# step_up_actuator.net
KiCad netlist of a schematic drawn in EAGLE
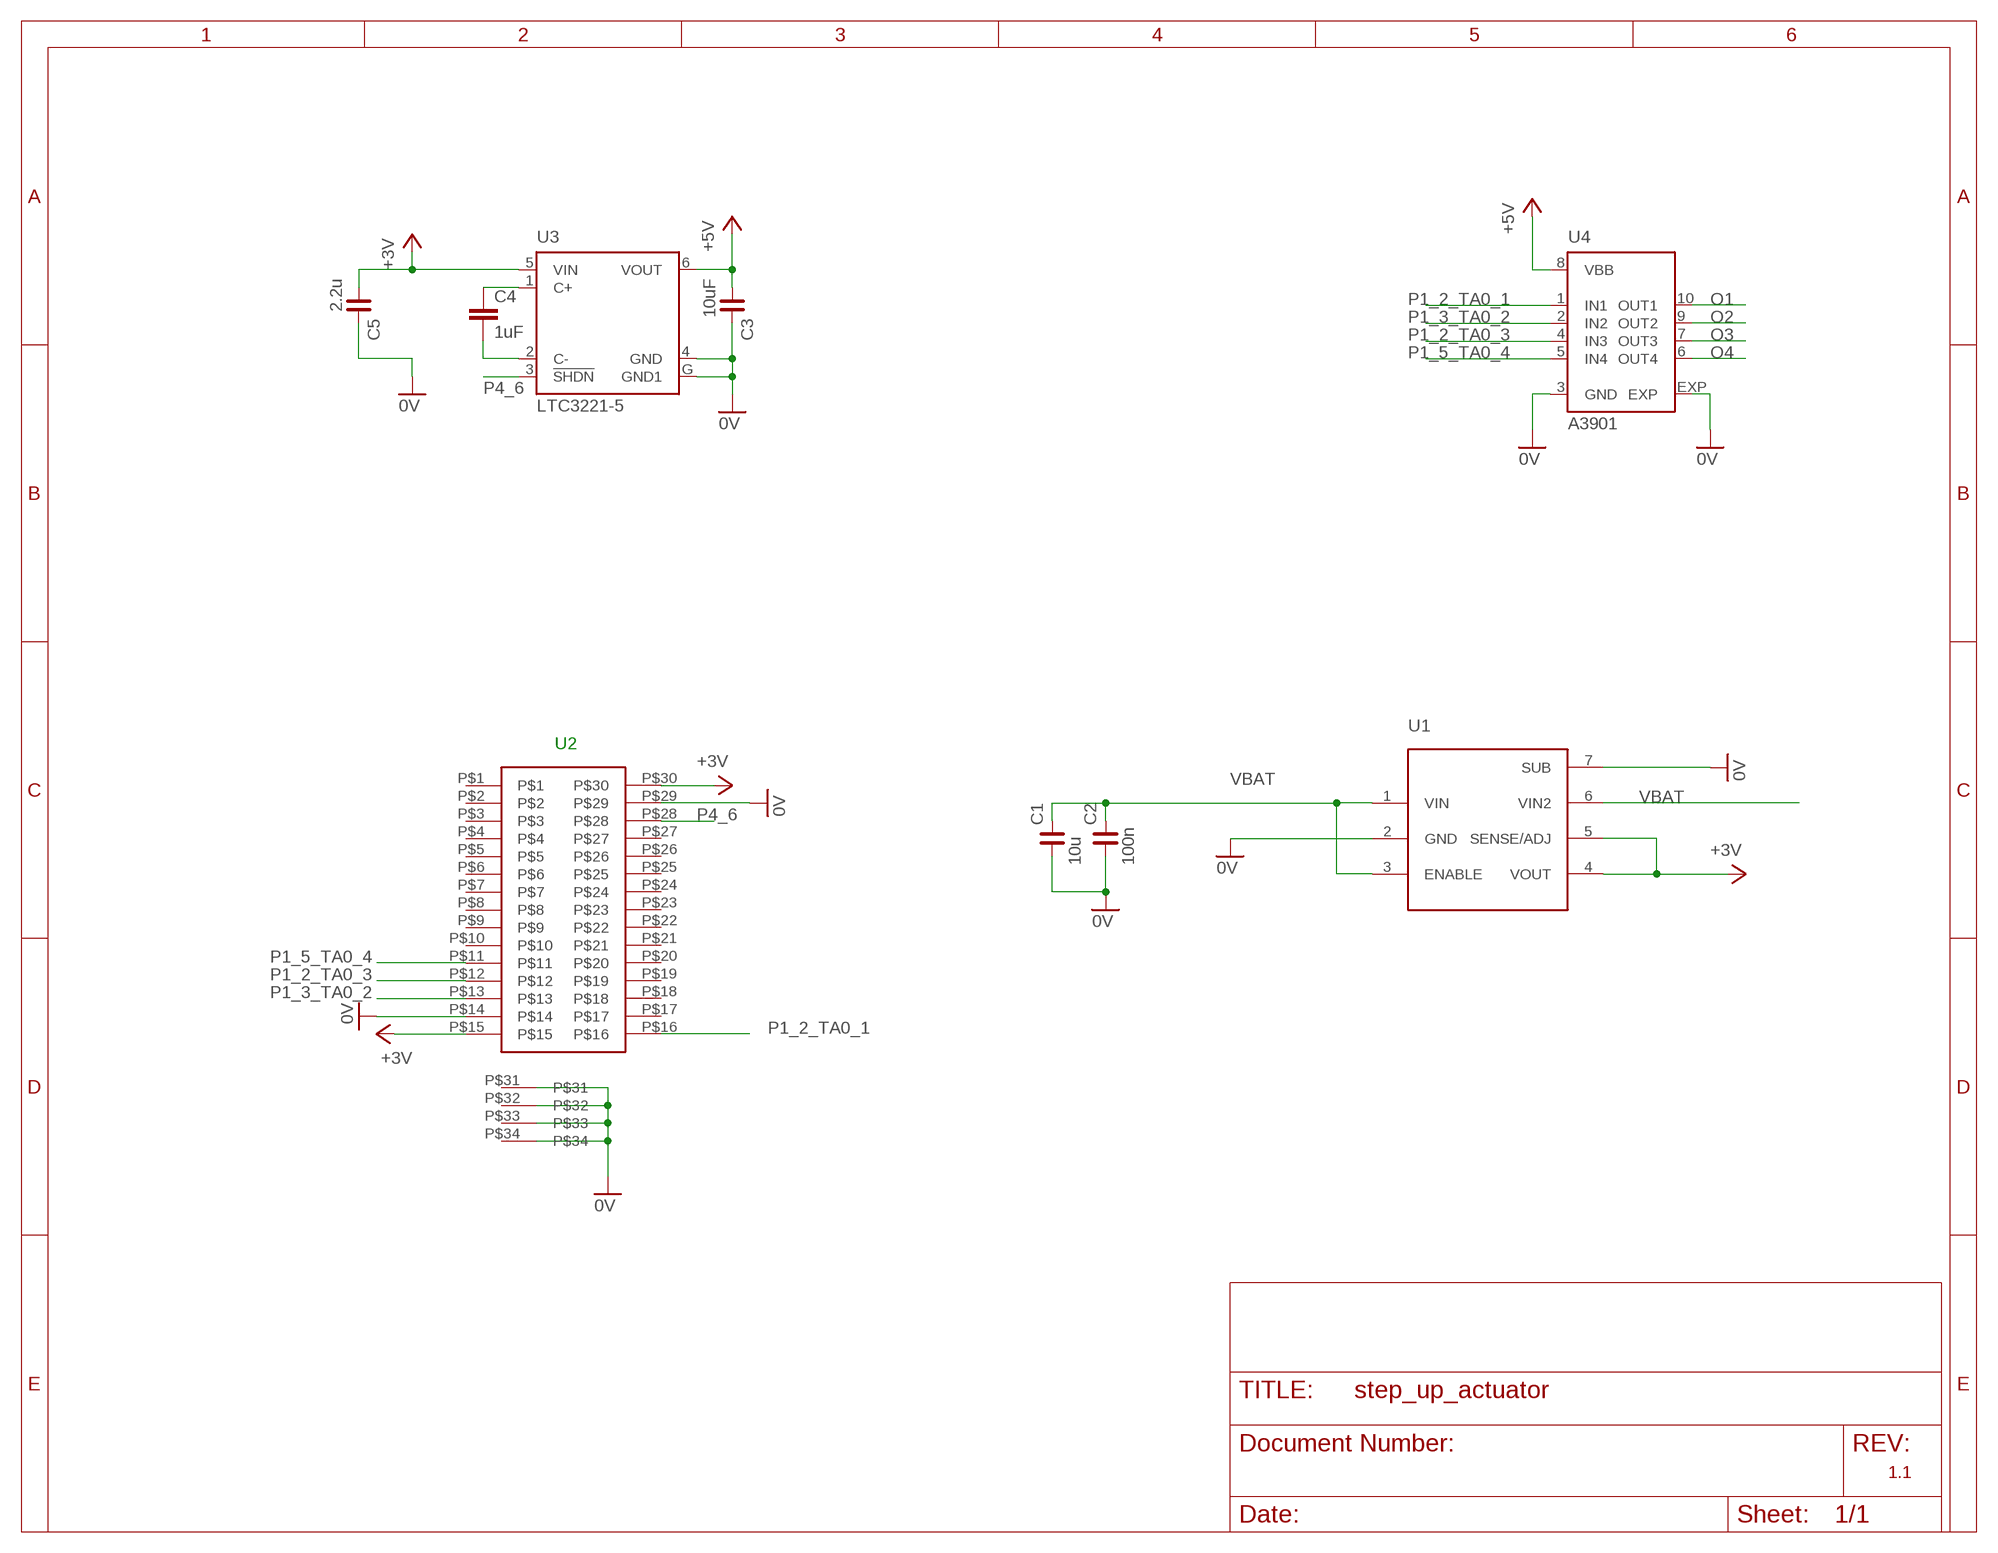
[diagram p0: schematic, sheet 1]

(export (version "E")
  (design (tool "Eeschema 10.0.6"))
  (components
    (comp (ref "C1")
      (value "10u")
      (footprint "eagle-import:C0402")
      (libsource (lib "eagle-import") (part "C_0402"))
    )
    (comp (ref "C2")
      (value "100n")
      (footprint "eagle-import:C0402")
      (libsource (lib "eagle-import") (part "C_0402"))
    )
    (comp (ref "C3")
      (value "10uF")
      (footprint "eagle-import:C1206")
      (libsource (lib "eagle-import") (part "C_1206"))
    )
    (comp (ref "C4")
      (value "1uF")
      (footprint "eagle-import:C0402")
      (libsource (lib "eagle-import") (part "C-EUC0402"))
    )
    (comp (ref "C5")
      (value "2.2u")
      (footprint "eagle-import:C0402")
      (libsource (lib "eagle-import") (part "C_0402"))
    )
    (comp (ref "U$1")
      (value "NCP606")
      (footprint "eagle-import:NCP606")
      (libsource (lib "eagle-import") (part "NCP606"))
    )
    (comp (ref "U$3")
      (value "51338-0374_RECEPTACLE")
      (footprint "eagle-import:51338-0374_RECEPTACLE")
      (libsource (lib "eagle-import") (part "51338-0374_RECEPTACLE"))
    )
    (comp (ref "U3")
      (value "LTC3221-5")
      (footprint "eagle-import:DFN6-2X2")
      (libsource (lib "eagle-import") (part "LTC3221-5"))
    )
    (comp (ref "U4")
      (value "A3901")
      (footprint "eagle-import:DFN10-3X3")
      (fields (field (name "MPN") "A3901SEJTR-T"))
      (libsource (lib "eagle-import") (part "A3901"))
    )
  )
  (nets
    (net (code "1") (name "+3V") (class "Default")
      (node (ref "C5") (pin "1") (pinfunction "1_1") (pintype "passive"))
      (node (ref "U$1") (pin "4") (pinfunction "VOUT_4") (pintype "bidirectional"))
      (node (ref "U$1") (pin "5") (pinfunction "SENSE/ADJ_5") (pintype "bidirectional"))
      (node (ref "U$3") (pin "P$15") (pinfunction "P$15_P$15") (pintype "bidirectional"))
      (node (ref "U$3") (pin "P$30") (pinfunction "P$30_P$30") (pintype "bidirectional"))
      (node (ref "U3") (pin "5") (pinfunction "VIN_5") (pintype "input"))
    )
    (net (code "2") (name "+5V") (class "Default")
      (node (ref "C3") (pin "1") (pinfunction "1_1") (pintype "passive"))
      (node (ref "U3") (pin "6") (pinfunction "VOUT_6") (pintype "output"))
      (node (ref "U4") (pin "8") (pinfunction "VBB_8") (pintype "power_in"))
    )
    (net (code "3") (name "/O1") (class "Default")
      (node (ref "U4") (pin "10") (pinfunction "OUT1_10") (pintype "output"))
    )
    (net (code "4") (name "/O2") (class "Default")
      (node (ref "U4") (pin "9") (pinfunction "OUT2_9") (pintype "output"))
    )
    (net (code "5") (name "/O3") (class "Default")
      (node (ref "U4") (pin "7") (pinfunction "OUT3_7") (pintype "output"))
    )
    (net (code "6") (name "/O4") (class "Default")
      (node (ref "U4") (pin "6") (pinfunction "OUT4_6") (pintype "output"))
    )
    (net (code "7") (name "/P1_2_TA0_1") (class "Default")
      (node (ref "U$3") (pin "P$16") (pinfunction "P$16_P$16") (pintype "bidirectional"))
      (node (ref "U4") (pin "1") (pinfunction "IN1_1") (pintype "input"))
    )
    (net (code "8") (name "/P1_2_TA0_3") (class "Default")
      (node (ref "U$3") (pin "P$12") (pinfunction "P$12_P$12") (pintype "bidirectional"))
      (node (ref "U4") (pin "4") (pinfunction "IN3_4") (pintype "input"))
    )
    (net (code "9") (name "/P1_3_TA0_2") (class "Default")
      (node (ref "U$3") (pin "P$13") (pinfunction "P$13_P$13") (pintype "bidirectional"))
      (node (ref "U4") (pin "2") (pinfunction "IN2_2") (pintype "input"))
    )
    (net (code "10") (name "/P1_5_TA0_4") (class "Default")
      (node (ref "U$3") (pin "P$11") (pinfunction "P$11_P$11") (pintype "bidirectional"))
      (node (ref "U4") (pin "5") (pinfunction "IN4_5") (pintype "input"))
    )
    (net (code "11") (name "/P4_6") (class "Default")
      (node (ref "U$3") (pin "P$28") (pinfunction "P$28_P$28") (pintype "bidirectional"))
      (node (ref "U3") (pin "3") (pinfunction "~{SHDN}_3") (pintype "input"))
    )
    (net (code "12") (name "/VBAT") (class "Default")
      (node (ref "C1") (pin "2") (pinfunction "2_2") (pintype "passive"))
      (node (ref "C2") (pin "2") (pinfunction "2_2") (pintype "passive"))
      (node (ref "U$1") (pin "1") (pinfunction "VIN_1") (pintype "bidirectional"))
      (node (ref "U$1") (pin "3") (pinfunction "ENABLE_3") (pintype "bidirectional"))
      (node (ref "U$1") (pin "6") (pinfunction "VIN2_6") (pintype "bidirectional"))
    )
    (net (code "13") (name "0V") (class "Default")
      (node (ref "C1") (pin "1") (pinfunction "1_1") (pintype "passive"))
      (node (ref "C2") (pin "1") (pinfunction "1_1") (pintype "passive"))
      (node (ref "C3") (pin "2") (pinfunction "2_2") (pintype "passive"))
      (node (ref "C5") (pin "2") (pinfunction "2_2") (pintype "passive"))
      (node (ref "U$1") (pin "2") (pinfunction "GND_2") (pintype "bidirectional"))
      (node (ref "U$1") (pin "7") (pinfunction "SUB_7") (pintype "bidirectional"))
      (node (ref "U$3") (pin "P$14") (pinfunction "P$14_P$14") (pintype "bidirectional"))
      (node (ref "U$3") (pin "P$29") (pinfunction "P$29_P$29") (pintype "bidirectional"))
      (node (ref "U3") (pin "4") (pinfunction "GND_4") (pintype "power_in"))
      (node (ref "U3") (pin "G") (pinfunction "GND1_G") (pintype "power_in"))
      (node (ref "U4") (pin "3") (pinfunction "GND_3") (pintype "power_in"))
      (node (ref "U4") (pin "EXP") (pinfunction "EXP_EXP") (pintype "passive"))
    )
    (net (code "14") (name "Net-(U3-C+)") (class "Default")
      (node (ref "C4") (pin "1") (pinfunction "1_1") (pintype "passive"))
      (node (ref "U3") (pin "1") (pinfunction "C+_1") (pintype "input"))
    )
    (net (code "15") (name "Net-(U3-C-)") (class "Default")
      (node (ref "C4") (pin "2") (pinfunction "2_2") (pintype "passive"))
      (node (ref "U3") (pin "2") (pinfunction "C-_2") (pintype "input"))
    )
    (net (code "16") (name "unconnected-(U$3-PadP$1)") (class "Default")
      (node (ref "U$3") (pin "P$1") (pinfunction "P$1_P$1") (pintype "bidirectional"))
    )
    (net (code "17") (name "unconnected-(U$3-PadP$2)") (class "Default")
      (node (ref "U$3") (pin "P$2") (pinfunction "P$2_P$2") (pintype "bidirectional"))
    )
    (net (code "18") (name "unconnected-(U$3-PadP$3)") (class "Default")
      (node (ref "U$3") (pin "P$3") (pinfunction "P$3_P$3") (pintype "bidirectional"))
    )
    (net (code "19") (name "unconnected-(U$3-PadP$4)") (class "Default")
      (node (ref "U$3") (pin "P$4") (pinfunction "P$4_P$4") (pintype "bidirectional"))
    )
    (net (code "20") (name "unconnected-(U$3-PadP$5)") (class "Default")
      (node (ref "U$3") (pin "P$5") (pinfunction "P$5_P$5") (pintype "bidirectional"))
    )
    (net (code "21") (name "unconnected-(U$3-PadP$6)") (class "Default")
      (node (ref "U$3") (pin "P$6") (pinfunction "P$6_P$6") (pintype "bidirectional"))
    )
    (net (code "22") (name "unconnected-(U$3-PadP$7)") (class "Default")
      (node (ref "U$3") (pin "P$7") (pinfunction "P$7_P$7") (pintype "bidirectional"))
    )
    (net (code "23") (name "unconnected-(U$3-PadP$8)") (class "Default")
      (node (ref "U$3") (pin "P$8") (pinfunction "P$8_P$8") (pintype "bidirectional"))
    )
    (net (code "24") (name "unconnected-(U$3-PadP$9)") (class "Default")
      (node (ref "U$3") (pin "P$9") (pinfunction "P$9_P$9") (pintype "bidirectional"))
    )
    (net (code "25") (name "unconnected-(U$3-PadP$10)") (class "Default")
      (node (ref "U$3") (pin "P$10") (pinfunction "P$10_P$10") (pintype "bidirectional"))
    )
    (net (code "26") (name "unconnected-(U$3-PadP$17)") (class "Default")
      (node (ref "U$3") (pin "P$17") (pinfunction "P$17_P$17") (pintype "bidirectional"))
    )
    (net (code "27") (name "unconnected-(U$3-PadP$18)") (class "Default")
      (node (ref "U$3") (pin "P$18") (pinfunction "P$18_P$18") (pintype "bidirectional"))
    )
    (net (code "28") (name "unconnected-(U$3-PadP$19)") (class "Default")
      (node (ref "U$3") (pin "P$19") (pinfunction "P$19_P$19") (pintype "bidirectional"))
    )
    (net (code "29") (name "unconnected-(U$3-PadP$20)") (class "Default")
      (node (ref "U$3") (pin "P$20") (pinfunction "P$20_P$20") (pintype "bidirectional"))
    )
    (net (code "30") (name "unconnected-(U$3-PadP$21)") (class "Default")
      (node (ref "U$3") (pin "P$21") (pinfunction "P$21_P$21") (pintype "bidirectional"))
    )
    (net (code "31") (name "unconnected-(U$3-PadP$22)") (class "Default")
      (node (ref "U$3") (pin "P$22") (pinfunction "P$22_P$22") (pintype "bidirectional"))
    )
    (net (code "32") (name "unconnected-(U$3-PadP$23)") (class "Default")
      (node (ref "U$3") (pin "P$23") (pinfunction "P$23_P$23") (pintype "bidirectional"))
    )
    (net (code "33") (name "unconnected-(U$3-PadP$24)") (class "Default")
      (node (ref "U$3") (pin "P$24") (pinfunction "P$24_P$24") (pintype "bidirectional"))
    )
    (net (code "34") (name "unconnected-(U$3-PadP$25)") (class "Default")
      (node (ref "U$3") (pin "P$25") (pinfunction "P$25_P$25") (pintype "bidirectional"))
    )
    (net (code "35") (name "unconnected-(U$3-PadP$26)") (class "Default")
      (node (ref "U$3") (pin "P$26") (pinfunction "P$26_P$26") (pintype "bidirectional"))
    )
    (net (code "36") (name "unconnected-(U$3-PadP$27)") (class "Default")
      (node (ref "U$3") (pin "P$27") (pinfunction "P$27_P$27") (pintype "bidirectional"))
    )
    (net (code "37") (name "unconnected-(U$3-PadP$31)") (class "Default")
      (node (ref "U$3") (pin "P$31") (pinfunction "P$31_P$31") (pintype "bidirectional"))
    )
    (net (code "38") (name "unconnected-(U$3-PadP$32)") (class "Default")
      (node (ref "U$3") (pin "P$32") (pinfunction "P$32_P$32") (pintype "bidirectional"))
    )
    (net (code "39") (name "unconnected-(U$3-PadP$33)") (class "Default")
      (node (ref "U$3") (pin "P$33") (pinfunction "P$33_P$33") (pintype "bidirectional"))
    )
    (net (code "40") (name "unconnected-(U$3-PadP$34)") (class "Default")
      (node (ref "U$3") (pin "P$34") (pinfunction "P$34_P$34") (pintype "bidirectional"))
    )
  )
)
